# ProPrj.net
KiCad netlist of a schematic drawn in EasyEDA Pro
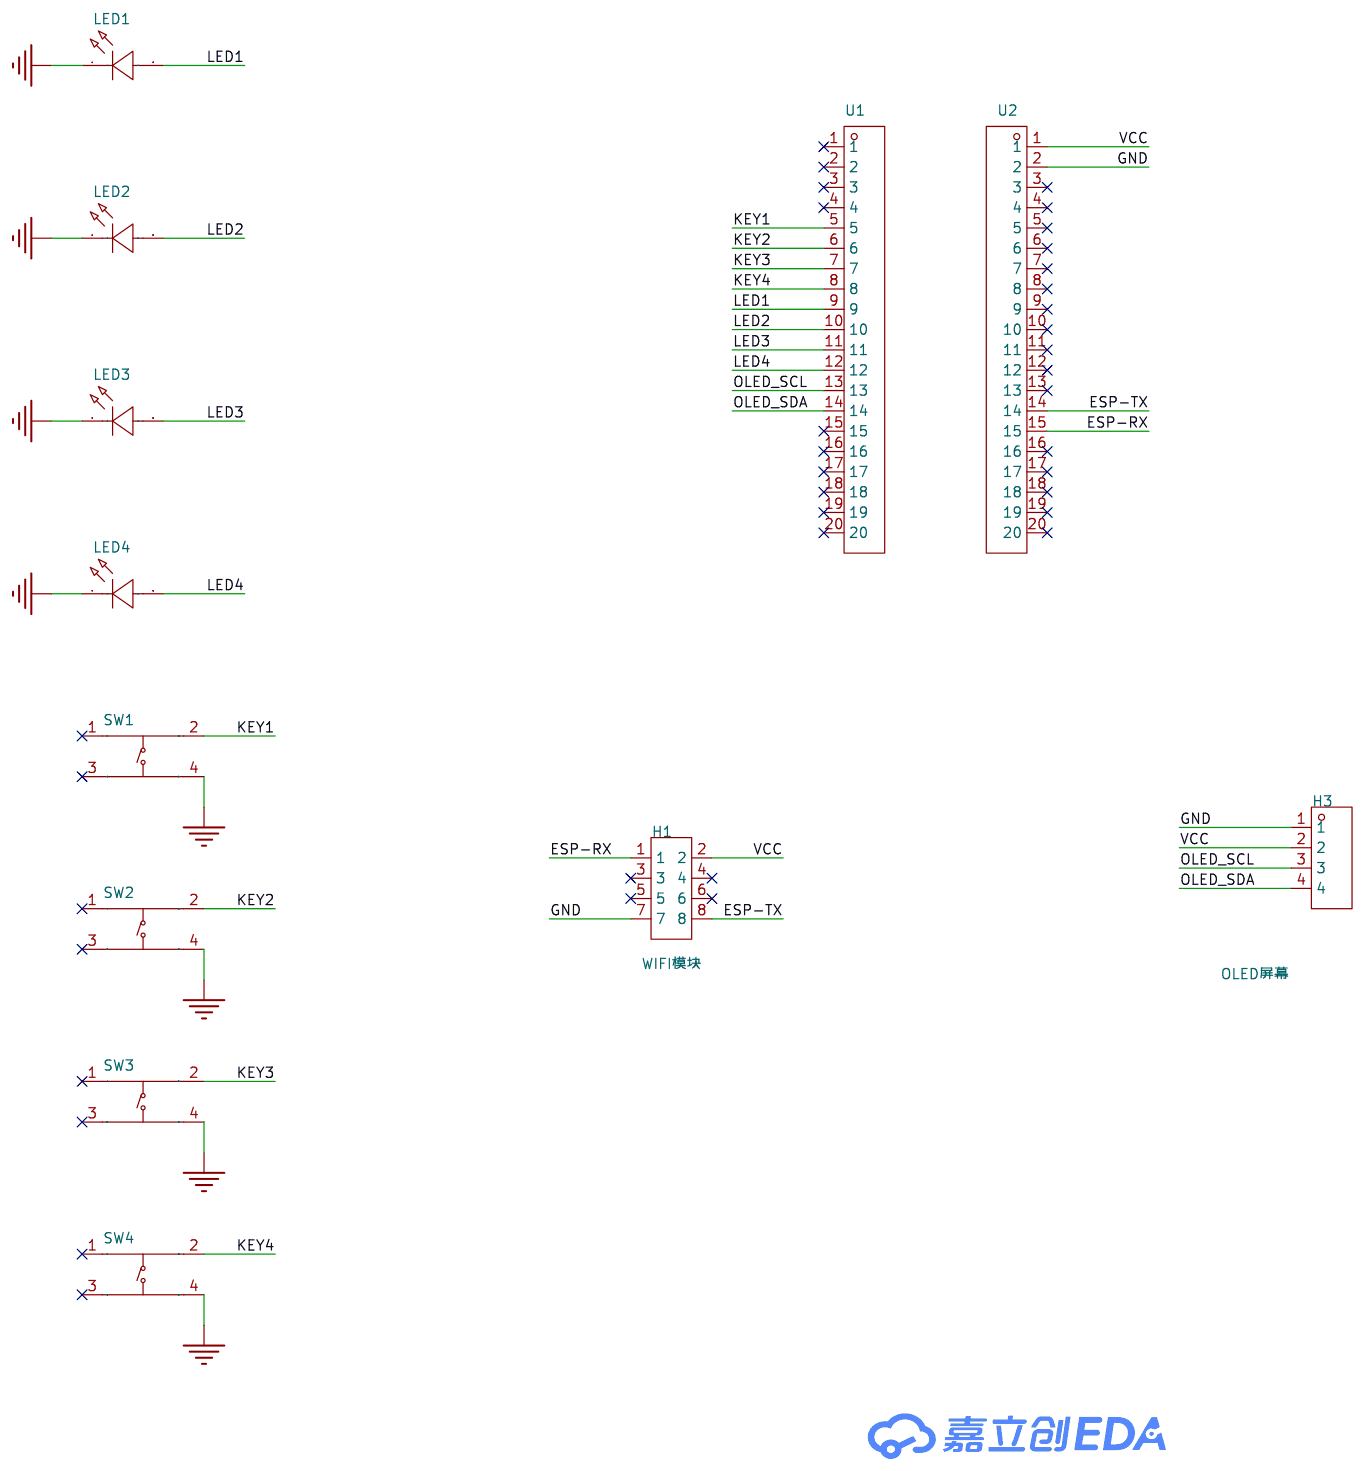
[diagram p0: schematic sheet]

(export (version "E")
  (design (tool "Eeschema 10.0.6"))
  (components
    (comp (ref "H1")
      (value "WIFI模块")
      (footprint "easyedapro:HDR-TH_8P-P2.54-V-M-R2-C4-S2.54")
      (fields (field (name "Manufacturer") "XFCN(兴飞)"))
      (libsource (lib "easyedapro") (part "PZ254V-12-8P"))
    )
    (comp (ref "H3")
      (value "OLED屏幕")
      (footprint "easyedapro:HDR-TH_4P-P2.54-V-M")
      (fields (field (name "Manufacturer") "XFCN(兴飞)"))
      (libsource (lib "easyedapro") (part "PZ254V-11-04P_C2691448"))
    )
    (comp (ref "LED1")
      (value "XL-302SURD")
      (footprint "easyedapro:LED-TH_BD3.8-P2.54-RD")
      (fields (field (name "Manufacturer") "XINGLIGHT(成兴光)"))
      (libsource (lib "easyedapro") (part "XL-302SURD"))
    )
    (comp (ref "LED2")
      (value "XL-302SURD")
      (footprint "easyedapro:LED-TH_BD3.8-P2.54-RD")
      (fields (field (name "Manufacturer") "XINGLIGHT(成兴光)"))
      (libsource (lib "easyedapro") (part "XL-302SURD"))
    )
    (comp (ref "LED3")
      (value "XL-302SURD")
      (footprint "easyedapro:LED-TH_BD3.8-P2.54-RD")
      (fields (field (name "Manufacturer") "XINGLIGHT(成兴光)"))
      (libsource (lib "easyedapro") (part "XL-302SURD"))
    )
    (comp (ref "LED4")
      (value "XL-302SURD")
      (footprint "easyedapro:LED-TH_BD3.8-P2.54-RD")
      (fields (field (name "Manufacturer") "XINGLIGHT(成兴光)"))
      (libsource (lib "easyedapro") (part "XL-302SURD"))
    )
    (comp (ref "SW1")
      (value "TS665CJ")
      (footprint "easyedapro:SW-TH_4P-L6.0-W6.0-P4.50-LS6.5")
      (description "电路结构:单刀单掷;按钮形状:圆形按钮;安装方式:直插;开关长度:6mm;开关宽度:6mm;开关高度:5mm;触点电流:50mA;额定电压(DC):12V;带灯:-;机械寿命:-;")
      (fields (field (name "Manufacturer") "SHOU HAN(首韩)"))
      (libsource (lib "easyedapro") (part "TS665CJ"))
    )
    (comp (ref "SW2")
      (value "TS665CJ")
      (footprint "easyedapro:SW-TH_4P-L6.0-W6.0-P4.50-LS6.5")
      (description "电路结构:单刀单掷;按钮形状:圆形按钮;安装方式:直插;开关长度:6mm;开关宽度:6mm;开关高度:5mm;触点电流:50mA;额定电压(DC):12V;带灯:-;机械寿命:-;")
      (fields (field (name "Manufacturer") "SHOU HAN(首韩)"))
      (libsource (lib "easyedapro") (part "TS665CJ"))
    )
    (comp (ref "SW3")
      (value "TS665CJ")
      (footprint "easyedapro:SW-TH_4P-L6.0-W6.0-P4.50-LS6.5")
      (description "电路结构:单刀单掷;按钮形状:圆形按钮;安装方式:直插;开关长度:6mm;开关宽度:6mm;开关高度:5mm;触点电流:50mA;额定电压(DC):12V;带灯:-;机械寿命:-;")
      (fields (field (name "Manufacturer") "SHOU HAN(首韩)"))
      (libsource (lib "easyedapro") (part "TS665CJ"))
    )
    (comp (ref "SW4")
      (value "TS665CJ")
      (footprint "easyedapro:SW-TH_4P-L6.0-W6.0-P4.50-LS6.5")
      (description "电路结构:单刀单掷;按钮形状:圆形按钮;安装方式:直插;开关长度:6mm;开关宽度:6mm;开关高度:5mm;触点电流:50mA;额定电压(DC):12V;带灯:-;机械寿命:-;")
      (fields (field (name "Manufacturer") "SHOU HAN(首韩)"))
      (libsource (lib "easyedapro") (part "TS665CJ"))
    )
    (comp (ref "U1")
      (value "ZX-PM2.54-1-20PY")
      (footprint "easyedapro:HDR-TH_20P-P2.54-V-F")
      (fields (field (name "Manufacturer") "Megastar(兆星)"))
      (libsource (lib "easyedapro") (part "ZX-PM2.54-1-20PY"))
    )
    (comp (ref "U2")
      (value "ZX-PM2.54-1-20PY")
      (footprint "easyedapro:HDR-TH_20P-P2.54-V-F")
      (fields (field (name "Manufacturer") "Megastar(兆星)"))
      (libsource (lib "easyedapro") (part "ZX-PM2.54-1-20PY"))
    )
  )
  (nets
    (net (code "1") (name "/ESP-RX") (class "Default")
      (node (ref "H1") (pin "1") (pinfunction "1_1") (pintype "unspecified"))
      (node (ref "U2") (pin "15") (pinfunction "15_15") (pintype "unspecified"))
    )
    (net (code "2") (name "/ESP-TX") (class "Default")
      (node (ref "H1") (pin "8") (pinfunction "8_8") (pintype "unspecified"))
      (node (ref "U2") (pin "14") (pinfunction "14_14") (pintype "unspecified"))
    )
    (net (code "3") (name "/KEY1") (class "Default")
      (node (ref "SW1") (pin "2") (pinfunction "B_2") (pintype "unspecified"))
      (node (ref "U1") (pin "5") (pinfunction "5_5") (pintype "unspecified"))
    )
    (net (code "4") (name "/KEY2") (class "Default")
      (node (ref "SW2") (pin "2") (pinfunction "B_2") (pintype "unspecified"))
      (node (ref "U1") (pin "6") (pinfunction "6_6") (pintype "unspecified"))
    )
    (net (code "5") (name "/KEY3") (class "Default")
      (node (ref "SW3") (pin "2") (pinfunction "B_2") (pintype "unspecified"))
      (node (ref "U1") (pin "7") (pinfunction "7_7") (pintype "unspecified"))
    )
    (net (code "6") (name "/KEY4") (class "Default")
      (node (ref "SW4") (pin "2") (pinfunction "B_2") (pintype "unspecified"))
      (node (ref "U1") (pin "8") (pinfunction "8_8") (pintype "unspecified"))
    )
    (net (code "7") (name "/LED1") (class "Default")
      (node (ref "LED1") (pin "2") (pinfunction "A_2") (pintype "unspecified"))
      (node (ref "U1") (pin "9") (pinfunction "9_9") (pintype "unspecified"))
    )
    (net (code "8") (name "/LED2") (class "Default")
      (node (ref "LED2") (pin "2") (pinfunction "A_2") (pintype "unspecified"))
      (node (ref "U1") (pin "10") (pinfunction "10_10") (pintype "unspecified"))
    )
    (net (code "9") (name "/LED3") (class "Default")
      (node (ref "LED3") (pin "2") (pinfunction "A_2") (pintype "unspecified"))
      (node (ref "U1") (pin "11") (pinfunction "11_11") (pintype "unspecified"))
    )
    (net (code "10") (name "/LED4") (class "Default")
      (node (ref "LED4") (pin "2") (pinfunction "A_2") (pintype "unspecified"))
      (node (ref "U1") (pin "12") (pinfunction "12_12") (pintype "unspecified"))
    )
    (net (code "11") (name "/OLED_SCL") (class "Default")
      (node (ref "H3") (pin "3") (pinfunction "3_3") (pintype "unspecified"))
      (node (ref "U1") (pin "13") (pinfunction "13_13") (pintype "unspecified"))
    )
    (net (code "12") (name "/OLED_SDA") (class "Default")
      (node (ref "H3") (pin "4") (pinfunction "4_4") (pintype "unspecified"))
      (node (ref "U1") (pin "14") (pinfunction "14_14") (pintype "unspecified"))
    )
    (net (code "13") (name "/VCC") (class "Default")
      (node (ref "H1") (pin "2") (pinfunction "2_2") (pintype "unspecified"))
      (node (ref "H3") (pin "2") (pinfunction "2_2") (pintype "unspecified"))
      (node (ref "U2") (pin "1") (pinfunction "1_1") (pintype "unspecified"))
    )
    (net (code "14") (name "GND") (class "Default")
      (node (ref "H1") (pin "7") (pinfunction "7_7") (pintype "unspecified"))
      (node (ref "H3") (pin "1") (pinfunction "1_1") (pintype "unspecified"))
      (node (ref "LED1") (pin "1") (pinfunction "K_1") (pintype "unspecified"))
      (node (ref "LED2") (pin "1") (pinfunction "K_1") (pintype "unspecified"))
      (node (ref "LED3") (pin "1") (pinfunction "K_1") (pintype "unspecified"))
      (node (ref "LED4") (pin "1") (pinfunction "K_1") (pintype "unspecified"))
      (node (ref "SW1") (pin "4") (pinfunction "D_4") (pintype "unspecified"))
      (node (ref "SW2") (pin "4") (pinfunction "D_4") (pintype "unspecified"))
      (node (ref "SW3") (pin "4") (pinfunction "D_4") (pintype "unspecified"))
      (node (ref "SW4") (pin "4") (pinfunction "D_4") (pintype "unspecified"))
      (node (ref "U2") (pin "2") (pinfunction "2_2") (pintype "unspecified"))
    )
    (net (code "15") (name "unconnected-(H1-Pad3)") (class "Default")
      (node (ref "H1") (pin "3") (pinfunction "3_3") (pintype "unspecified+no_connect"))
    )
    (net (code "16") (name "unconnected-(H1-Pad4)") (class "Default")
      (node (ref "H1") (pin "4") (pinfunction "4_4") (pintype "unspecified+no_connect"))
    )
    (net (code "17") (name "unconnected-(H1-Pad5)") (class "Default")
      (node (ref "H1") (pin "5") (pinfunction "5_5") (pintype "unspecified+no_connect"))
    )
    (net (code "18") (name "unconnected-(H1-Pad6)") (class "Default")
      (node (ref "H1") (pin "6") (pinfunction "6_6") (pintype "unspecified+no_connect"))
    )
    (net (code "19") (name "unconnected-(SW1-A-Pad1)") (class "Default")
      (node (ref "SW1") (pin "1") (pinfunction "A_1") (pintype "unspecified+no_connect"))
    )
    (net (code "20") (name "unconnected-(SW1-C-Pad3)") (class "Default")
      (node (ref "SW1") (pin "3") (pinfunction "C_3") (pintype "unspecified+no_connect"))
    )
    (net (code "21") (name "unconnected-(SW2-A-Pad1)") (class "Default")
      (node (ref "SW2") (pin "1") (pinfunction "A_1") (pintype "unspecified+no_connect"))
    )
    (net (code "22") (name "unconnected-(SW2-C-Pad3)") (class "Default")
      (node (ref "SW2") (pin "3") (pinfunction "C_3") (pintype "unspecified+no_connect"))
    )
    (net (code "23") (name "unconnected-(SW3-A-Pad1)") (class "Default")
      (node (ref "SW3") (pin "1") (pinfunction "A_1") (pintype "unspecified+no_connect"))
    )
    (net (code "24") (name "unconnected-(SW3-C-Pad3)") (class "Default")
      (node (ref "SW3") (pin "3") (pinfunction "C_3") (pintype "unspecified+no_connect"))
    )
    (net (code "25") (name "unconnected-(SW4-A-Pad1)") (class "Default")
      (node (ref "SW4") (pin "1") (pinfunction "A_1") (pintype "unspecified+no_connect"))
    )
    (net (code "26") (name "unconnected-(SW4-C-Pad3)") (class "Default")
      (node (ref "SW4") (pin "3") (pinfunction "C_3") (pintype "unspecified+no_connect"))
    )
    (net (code "27") (name "unconnected-(U1-Pad1)") (class "Default")
      (node (ref "U1") (pin "1") (pinfunction "1_1") (pintype "unspecified+no_connect"))
    )
    (net (code "28") (name "unconnected-(U1-Pad2)") (class "Default")
      (node (ref "U1") (pin "2") (pinfunction "2_2") (pintype "unspecified+no_connect"))
    )
    (net (code "29") (name "unconnected-(U1-Pad3)") (class "Default")
      (node (ref "U1") (pin "3") (pinfunction "3_3") (pintype "unspecified+no_connect"))
    )
    (net (code "30") (name "unconnected-(U1-Pad4)") (class "Default")
      (node (ref "U1") (pin "4") (pinfunction "4_4") (pintype "unspecified+no_connect"))
    )
    (net (code "31") (name "unconnected-(U1-Pad15)") (class "Default")
      (node (ref "U1") (pin "15") (pinfunction "15_15") (pintype "unspecified+no_connect"))
    )
    (net (code "32") (name "unconnected-(U1-Pad16)") (class "Default")
      (node (ref "U1") (pin "16") (pinfunction "16_16") (pintype "unspecified+no_connect"))
    )
    (net (code "33") (name "unconnected-(U1-Pad17)") (class "Default")
      (node (ref "U1") (pin "17") (pinfunction "17_17") (pintype "unspecified+no_connect"))
    )
    (net (code "34") (name "unconnected-(U1-Pad18)") (class "Default")
      (node (ref "U1") (pin "18") (pinfunction "18_18") (pintype "unspecified+no_connect"))
    )
    (net (code "35") (name "unconnected-(U1-Pad19)") (class "Default")
      (node (ref "U1") (pin "19") (pinfunction "19_19") (pintype "unspecified+no_connect"))
    )
    (net (code "36") (name "unconnected-(U1-Pad20)") (class "Default")
      (node (ref "U1") (pin "20") (pinfunction "20_20") (pintype "unspecified+no_connect"))
    )
    (net (code "37") (name "unconnected-(U2-Pad3)") (class "Default")
      (node (ref "U2") (pin "3") (pinfunction "3_3") (pintype "unspecified+no_connect"))
    )
    (net (code "38") (name "unconnected-(U2-Pad4)") (class "Default")
      (node (ref "U2") (pin "4") (pinfunction "4_4") (pintype "unspecified+no_connect"))
    )
    (net (code "39") (name "unconnected-(U2-Pad5)") (class "Default")
      (node (ref "U2") (pin "5") (pinfunction "5_5") (pintype "unspecified+no_connect"))
    )
    (net (code "40") (name "unconnected-(U2-Pad6)") (class "Default")
      (node (ref "U2") (pin "6") (pinfunction "6_6") (pintype "unspecified+no_connect"))
    )
    (net (code "41") (name "unconnected-(U2-Pad7)") (class "Default")
      (node (ref "U2") (pin "7") (pinfunction "7_7") (pintype "unspecified+no_connect"))
    )
    (net (code "42") (name "unconnected-(U2-Pad8)") (class "Default")
      (node (ref "U2") (pin "8") (pinfunction "8_8") (pintype "unspecified+no_connect"))
    )
    (net (code "43") (name "unconnected-(U2-Pad9)") (class "Default")
      (node (ref "U2") (pin "9") (pinfunction "9_9") (pintype "unspecified+no_connect"))
    )
    (net (code "44") (name "unconnected-(U2-Pad10)") (class "Default")
      (node (ref "U2") (pin "10") (pinfunction "10_10") (pintype "unspecified+no_connect"))
    )
    (net (code "45") (name "unconnected-(U2-Pad11)") (class "Default")
      (node (ref "U2") (pin "11") (pinfunction "11_11") (pintype "unspecified+no_connect"))
    )
    (net (code "46") (name "unconnected-(U2-Pad12)") (class "Default")
      (node (ref "U2") (pin "12") (pinfunction "12_12") (pintype "unspecified+no_connect"))
    )
    (net (code "47") (name "unconnected-(U2-Pad13)") (class "Default")
      (node (ref "U2") (pin "13") (pinfunction "13_13") (pintype "unspecified+no_connect"))
    )
    (net (code "48") (name "unconnected-(U2-Pad16)") (class "Default")
      (node (ref "U2") (pin "16") (pinfunction "16_16") (pintype "unspecified+no_connect"))
    )
    (net (code "49") (name "unconnected-(U2-Pad17)") (class "Default")
      (node (ref "U2") (pin "17") (pinfunction "17_17") (pintype "unspecified+no_connect"))
    )
    (net (code "50") (name "unconnected-(U2-Pad18)") (class "Default")
      (node (ref "U2") (pin "18") (pinfunction "18_18") (pintype "unspecified+no_connect"))
    )
    (net (code "51") (name "unconnected-(U2-Pad19)") (class "Default")
      (node (ref "U2") (pin "19") (pinfunction "19_19") (pintype "unspecified+no_connect"))
    )
    (net (code "52") (name "unconnected-(U2-Pad20)") (class "Default")
      (node (ref "U2") (pin "20") (pinfunction "20_20") (pintype "unspecified+no_connect"))
    )
  )
)
